# design.net
KiCad netlist of a schematic drawn in Altium Designer
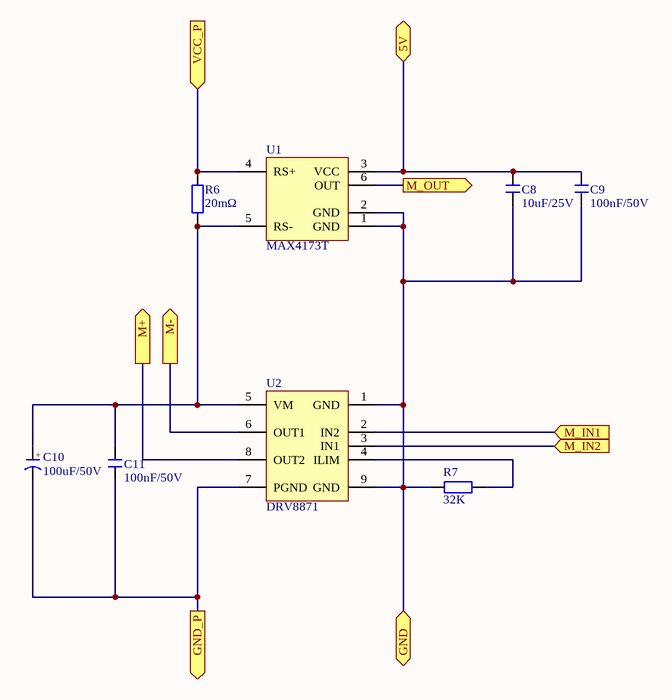
[diagram p0: 电机驱动_电流检测原理图.SchDoc]

(export (version "E")
  (design (tool "Eeschema 10.0.6"))
  (components
    (comp (ref "C8")
      (value "10uF/25V")
      (footprint "C 0603_M")
      (description "无极性贴片电容")
      (fields (field (name "版权归属") "源创客"))
      (libsource (lib "3.1   - 电阻-电容-电感") (part "C"))
    )
    (comp (ref "C9")
      (value "100nF/50V")
      (footprint "C 0603_M")
      (description "无极性贴片电容")
      (fields (field (name "版权归属") "源创客"))
      (libsource (lib "3.1   - 电阻-电容-电感") (part "C"))
    )
    (comp (ref "C10")
      (value "100uF/50V")
      (footprint "CAP 3.5*8*11.5")
      (description "直插电解电容")
      (fields (field (name "版权归属") "源创客"))
      (libsource (lib "3.1   - 电阻-电容-电感") (part "C-CAP"))
    )
    (comp (ref "C11")
      (value "100nF/50V")
      (footprint "C 0603_M")
      (description "无极性贴片电容")
      (fields (field (name "版权归属") "源创客"))
      (libsource (lib "3.1   - 电阻-电容-电感") (part "C"))
    )
    (comp (ref "R6")
      (value "20mΩ")
      (footprint "R 2512_M")
      (description "贴片电阻")
      (fields (field (name "版权归属") "源创客"))
      (libsource (lib "3.1   - 电阻-电容-电感") (part "R"))
    )
    (comp (ref "R7")
      (value "32K")
      (footprint "R 0603_M")
      (description "贴片电阻")
      (fields (field (name "版权归属") "源创客"))
      (libsource (lib "3.1   - 电阻-电容-电感") (part "R"))
    )
    (comp (ref "U1")
      (value "MAX4173T")
      (footprint "SOT23-6N")
      (description "高端电流检测")
      (fields (field (name "版权归属") "源创客"))
      (libsource (lib "1.1   - IC芯片") (part "MAX4173"))
    )
    (comp (ref "U2")
      (value "DRV8871")
      (footprint "ESOP8_N")
      (description "电机驱动芯片")
      (libsource (lib "1.1   - IC芯片") (part "DRV8872"))
    )
  )
  (nets
    (net (code "1") (name "/5V") (class "Default")
      (node (ref "C8") (pin "1") (pinfunction "1_1") (pintype "passive"))
      (node (ref "C9") (pin "1") (pinfunction "1_1") (pintype "passive"))
      (node (ref "U1") (pin "3") (pinfunction "VCC_3") (pintype "passive"))
    )
    (net (code "2") (name "/GND") (class "Default")
      (node (ref "C8") (pin "2") (pinfunction "2_2") (pintype "passive"))
      (node (ref "C9") (pin "2") (pinfunction "2_2") (pintype "passive"))
      (node (ref "R7") (pin "1") (pinfunction "1_1") (pintype "passive"))
      (node (ref "U1") (pin "1") (pinfunction "GND_1") (pintype "passive"))
      (node (ref "U1") (pin "2") (pinfunction "GND_2") (pintype "passive"))
      (node (ref "U2") (pin "1") (pinfunction "GND_1") (pintype "power_in"))
      (node (ref "U2") (pin "9") (pinfunction "GND_9") (pintype "power_in"))
    )
    (net (code "3") (name "/GND_P") (class "Default")
      (node (ref "C10") (pin "2") (pinfunction "K_2") (pintype "passive"))
      (node (ref "C11") (pin "1") (pinfunction "1_1") (pintype "passive"))
      (node (ref "U2") (pin "7") (pinfunction "PGND_7") (pintype "power_in"))
    )
    (net (code "4") (name "/M+") (class "Default")
      (node (ref "U2") (pin "8") (pinfunction "OUT2_8") (pintype "power_in"))
    )
    (net (code "5") (name "/M-") (class "Default")
      (node (ref "U2") (pin "6") (pinfunction "OUT1_6") (pintype "power_in"))
    )
    (net (code "6") (name "/M_IN1") (class "Default")
      (node (ref "U2") (pin "2") (pinfunction "IN2_2") (pintype "power_in"))
    )
    (net (code "7") (name "/M_IN2") (class "Default")
      (node (ref "U2") (pin "3") (pinfunction "IN1_3") (pintype "power_in"))
    )
    (net (code "8") (name "/M_OUT") (class "Default")
      (node (ref "U1") (pin "6") (pinfunction "OUT_6") (pintype "passive"))
    )
    (net (code "9") (name "/VCC_P") (class "Default")
      (node (ref "R6") (pin "1") (pinfunction "1_1") (pintype "passive"))
      (node (ref "U1") (pin "4") (pinfunction "RS+_4") (pintype "passive"))
    )
    (net (code "10") (name "Net-(C10-A)") (class "Default")
      (node (ref "C10") (pin "1") (pinfunction "A_1") (pintype "passive"))
      (node (ref "C11") (pin "2") (pinfunction "2_2") (pintype "passive"))
      (node (ref "R6") (pin "2") (pinfunction "2_2") (pintype "passive"))
      (node (ref "U1") (pin "5") (pinfunction "RS-_5") (pintype "passive"))
      (node (ref "U2") (pin "5") (pinfunction "VM_5") (pintype "power_in"))
    )
    (net (code "11") (name "Net-(U2-ILIM)") (class "Default")
      (node (ref "R7") (pin "2") (pinfunction "2_2") (pintype "passive"))
      (node (ref "U2") (pin "4") (pinfunction "ILIM_4") (pintype "power_in"))
    )
  )
)
